# power_sply.net
KiCad netlist of a schematic drawn in EAGLE
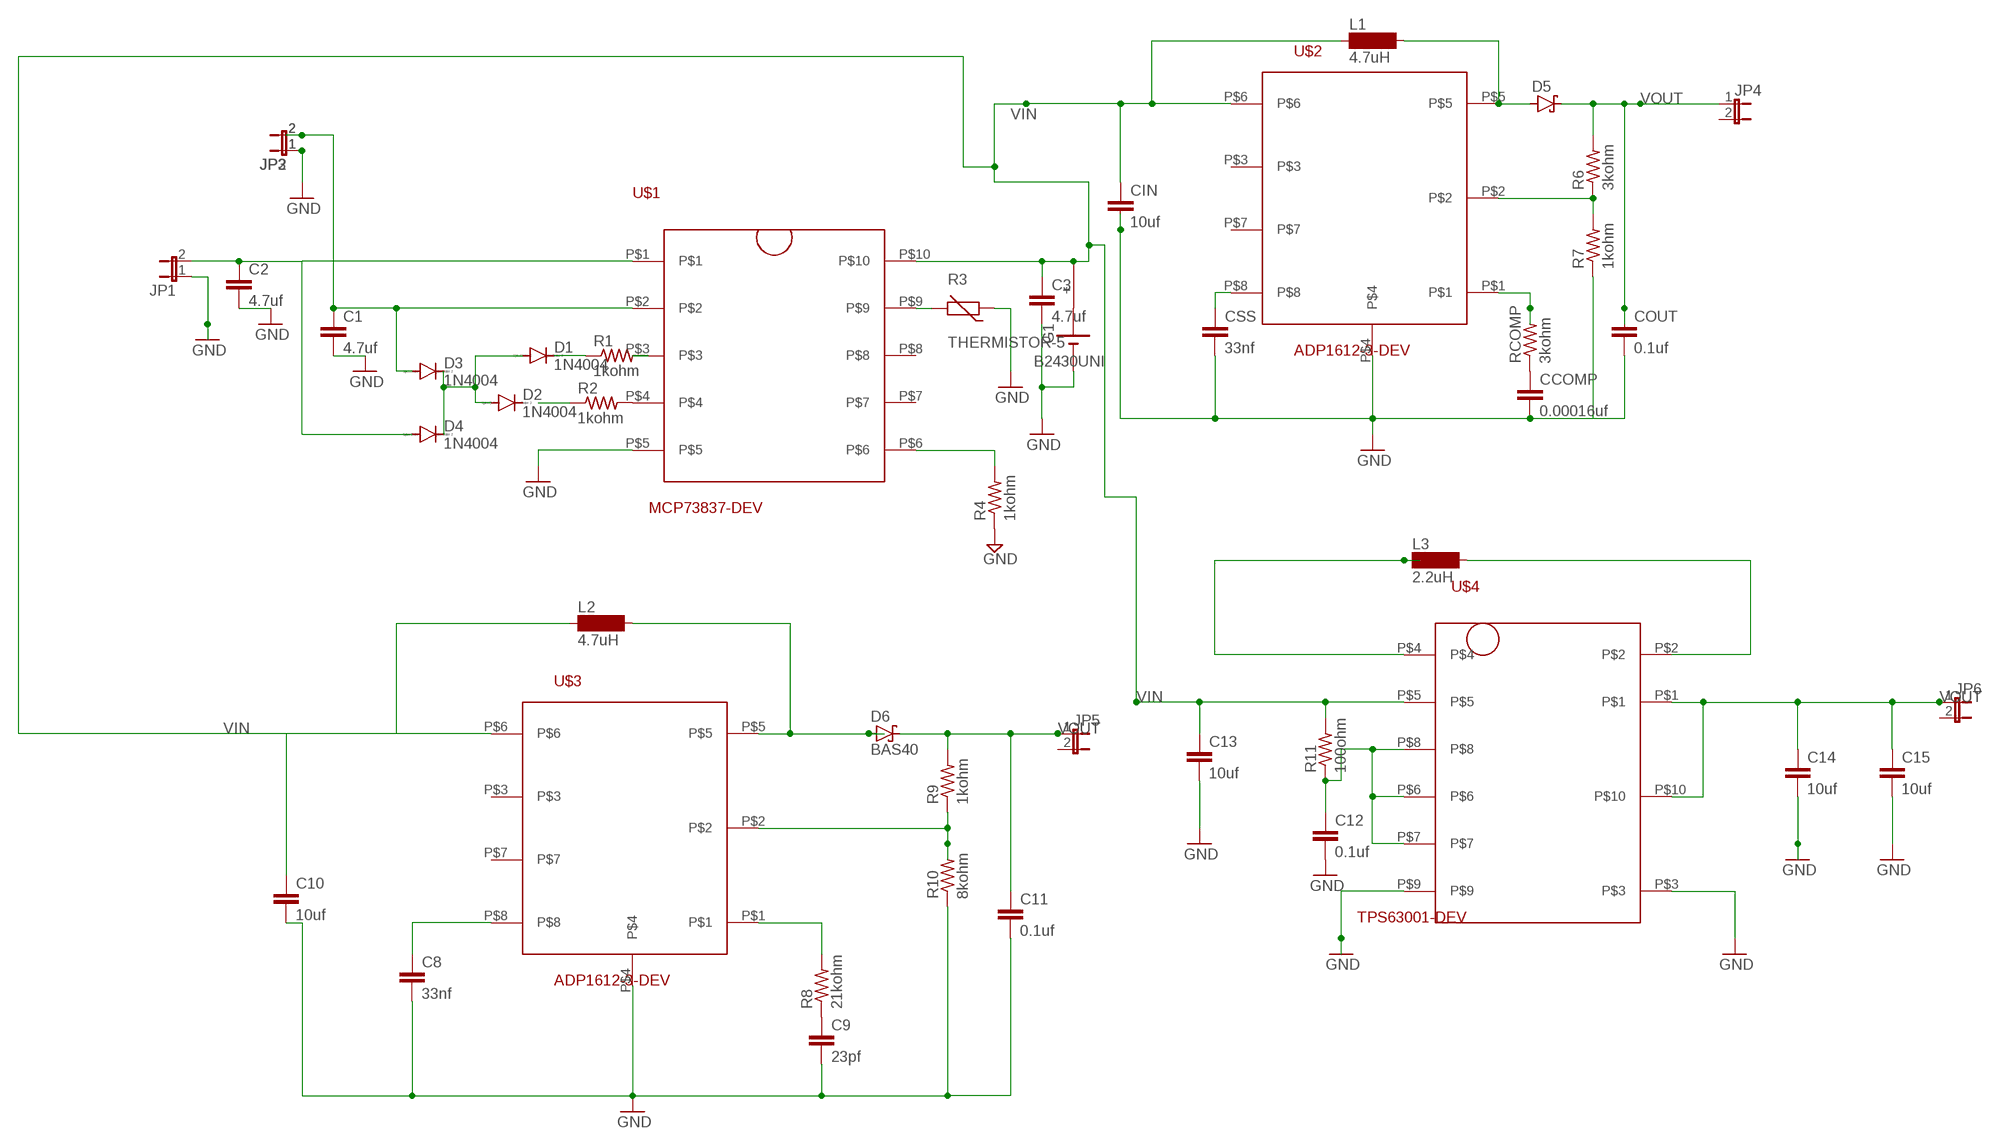
[diagram p0: schematic, sheet 1]

(export (version "E")
  (design (tool "Eeschema 10.0.6"))
  (components
    (comp (ref "C1")
      (value "4.7uf")
      (footprint "eagle-import:C2.5-3")
      (libsource (lib "eagle-import") (part "C2,5-3"))
    )
    (comp (ref "C2")
      (value "4.7uf")
      (footprint "eagle-import:C2.5-3")
      (libsource (lib "eagle-import") (part "C2,5-3"))
    )
    (comp (ref "C3")
      (value "4.7uf")
      (footprint "eagle-import:C2.5-3")
      (libsource (lib "eagle-import") (part "C2,5-3"))
    )
    (comp (ref "C8")
      (value "33nf")
      (footprint "eagle-import:C2.5-3")
      (libsource (lib "eagle-import") (part "C2,5-3"))
    )
    (comp (ref "C9")
      (value "23pf")
      (footprint "eagle-import:C2.5-3")
      (libsource (lib "eagle-import") (part "C2,5-3"))
    )
    (comp (ref "C10")
      (value "10uf")
      (footprint "eagle-import:C2.5-3")
      (libsource (lib "eagle-import") (part "C2,5-3"))
    )
    (comp (ref "C11")
      (value "0.1uf")
      (footprint "eagle-import:C2.5-3")
      (libsource (lib "eagle-import") (part "C2,5-3"))
    )
    (comp (ref "C12")
      (value "0.1uf")
      (footprint "eagle-import:C2.5-3")
      (libsource (lib "eagle-import") (part "C2,5-3"))
    )
    (comp (ref "C13")
      (value "10uf")
      (footprint "eagle-import:C2.5-3")
      (libsource (lib "eagle-import") (part "C2,5-3"))
    )
    (comp (ref "C14")
      (value "10uf")
      (footprint "eagle-import:C2.5-3")
      (libsource (lib "eagle-import") (part "C2,5-3"))
    )
    (comp (ref "C15")
      (value "10uf")
      (footprint "eagle-import:C2.5-3")
      (libsource (lib "eagle-import") (part "C2,5-3"))
    )
    (comp (ref "CCOMP")
      (value "0.00016uf")
      (footprint "eagle-import:C2.5-3")
      (libsource (lib "eagle-import") (part "C2,5-3"))
    )
    (comp (ref "CIN")
      (value "10uf")
      (footprint "eagle-import:C2.5-3")
      (libsource (lib "eagle-import") (part "C2,5-3"))
    )
    (comp (ref "COUT")
      (value "0.1uf")
      (footprint "eagle-import:C2.5-3")
      (libsource (lib "eagle-import") (part "C2,5-3"))
    )
    (comp (ref "CSS")
      (value "33nf")
      (footprint "eagle-import:C2.5-3")
      (libsource (lib "eagle-import") (part "C2,5-3"))
    )
    (comp (ref "D1")
      (value "1N4004")
      (footprint "eagle-import:DO41-10")
      (libsource (lib "eagle-import") (part "1N4004"))
    )
    (comp (ref "D2")
      (value "1N4004")
      (footprint "eagle-import:DO41-10")
      (libsource (lib "eagle-import") (part "1N4004"))
    )
    (comp (ref "D3")
      (value "1N4004")
      (footprint "eagle-import:DO41-10")
      (libsource (lib "eagle-import") (part "1N4004"))
    )
    (comp (ref "D4")
      (value "1N4004")
      (footprint "eagle-import:DO41-10")
      (libsource (lib "eagle-import") (part "1N4004"))
    )
    (comp (ref "D5")
      (value "BAS40")
      (footprint "eagle-import:SOT23")
      (libsource (lib "eagle-import") (part "BAS40"))
    )
    (comp (ref "D6")
      (value "BAS40")
      (footprint "eagle-import:SOT23")
      (libsource (lib "eagle-import") (part "BAS40"))
    )
    (comp (ref "G1")
      (value "B2430UNI")
      (footprint "eagle-import:B2430UNI")
      (libsource (lib "eagle-import") (part "B2430UNI"))
    )
    (comp (ref "JP1")
      (value "JP1E")
      (footprint "eagle-import:JP1")
      (libsource (lib "eagle-import") (part "JP1E"))
    )
    (comp (ref "JP2")
      (value "JP1E")
      (footprint "eagle-import:JP1")
      (libsource (lib "eagle-import") (part "JP1E"))
    )
    (comp (ref "JP3")
      (value "JP1E")
      (footprint "eagle-import:JP1")
      (libsource (lib "eagle-import") (part "JP1E"))
    )
    (comp (ref "JP4")
      (value "JP1E")
      (footprint "eagle-import:JP1")
      (libsource (lib "eagle-import") (part "JP1E"))
    )
    (comp (ref "JP5")
      (value "JP1E")
      (footprint "eagle-import:JP1")
      (libsource (lib "eagle-import") (part "JP1E"))
    )
    (comp (ref "JP6")
      (value "JP1E")
      (footprint "eagle-import:JP1")
      (libsource (lib "eagle-import") (part "JP1E"))
    )
    (comp (ref "L1")
      (value "4.7uH")
      (footprint "eagle-import:MS42")
      (libsource (lib "eagle-import") (part "MS42"))
    )
    (comp (ref "L2")
      (value "4.7uH")
      (footprint "eagle-import:MS42")
      (libsource (lib "eagle-import") (part "MS42"))
    )
    (comp (ref "L3")
      (value "2.2uH")
      (footprint "eagle-import:BS11")
      (libsource (lib "eagle-import") (part "BS11"))
    )
    (comp (ref "R1")
      (value "1kohm")
      (footprint "eagle-import:0204V")
      (libsource (lib "eagle-import") (part "R-US_0204/2V"))
    )
    (comp (ref "R2")
      (value "1kohm")
      (footprint "eagle-import:0204V")
      (libsource (lib "eagle-import") (part "R-US_0204/2V"))
    )
    (comp (ref "R3")
      (value "THERMISTOR-5")
      (footprint "eagle-import:R-5")
      (libsource (lib "eagle-import") (part "THERMISTOR-5"))
    )
    (comp (ref "R4")
      (value "1kohm")
      (footprint "eagle-import:0204V")
      (libsource (lib "eagle-import") (part "R-US_0204/2V"))
    )
    (comp (ref "R6")
      (value "3kohm")
      (footprint "eagle-import:0204V")
      (libsource (lib "eagle-import") (part "R-US_0204/2V"))
    )
    (comp (ref "R7")
      (value "1kohm")
      (footprint "eagle-import:0204V")
      (libsource (lib "eagle-import") (part "R-US_0204/2V"))
    )
    (comp (ref "R8")
      (value "21kohm")
      (footprint "eagle-import:0204V")
      (libsource (lib "eagle-import") (part "R-US_0204/2V"))
    )
    (comp (ref "R9")
      (value "1kohm")
      (footprint "eagle-import:0204V")
      (libsource (lib "eagle-import") (part "R-US_0204/2V"))
    )
    (comp (ref "R10")
      (value "8kohm")
      (footprint "eagle-import:0204V")
      (libsource (lib "eagle-import") (part "R-US_0204/2V"))
    )
    (comp (ref "R11")
      (value "100ohm")
      (footprint "eagle-import:0204V")
      (libsource (lib "eagle-import") (part "R-US_0204/2V"))
    )
    (comp (ref "RCOMP")
      (value "3kohm")
      (footprint "eagle-import:0204V")
      (libsource (lib "eagle-import") (part "R-US_0204/2V"))
    )
    (comp (ref "U$1")
      (value "MCP73837-DEV")
      (footprint "eagle-import:MCP73837-FOOT")
      (libsource (lib "eagle-import") (part "MCP73837-DEV"))
    )
    (comp (ref "U$2")
      (value "ADP1612-3-DEV")
      (footprint "eagle-import:ADP1612-3-FOOT")
      (libsource (lib "eagle-import") (part "ADP1612-3-DEV"))
    )
    (comp (ref "U$3")
      (value "ADP1612-3-DEV")
      (footprint "eagle-import:ADP1612-3-FOOT")
      (libsource (lib "eagle-import") (part "ADP1612-3-DEV"))
    )
    (comp (ref "U$4")
      (value "TPS63001-DEV")
      (footprint "eagle-import:TPS63001-FOOT")
      (libsource (lib "eagle-import") (part "TPS63001-DEV"))
    )
  )
  (nets
    (net (code "1") (name "/VIN") (class "Default")
      (node (ref "C10") (pin "1") (pinfunction "1_1") (pintype "passive"))
      (node (ref "C13") (pin "1") (pinfunction "1_1") (pintype "passive"))
      (node (ref "C3") (pin "1") (pinfunction "1_1") (pintype "passive"))
      (node (ref "CIN") (pin "1") (pinfunction "1_1") (pintype "passive"))
      (node (ref "G1") (pin "+") (pinfunction "+_+") (pintype "passive"))
      (node (ref "L1") (pin "1") (pinfunction "1_1") (pintype "passive"))
      (node (ref "L2") (pin "1") (pinfunction "1_1") (pintype "passive"))
      (node (ref "R11") (pin "2") (pinfunction "2_2") (pintype "passive"))
      (node (ref "U$1") (pin "P$10") (pinfunction "P$10_P$10") (pintype "bidirectional"))
      (node (ref "U$2") (pin "P$6") (pinfunction "P$6_P$6") (pintype "bidirectional"))
      (node (ref "U$3") (pin "P$6") (pinfunction "P$6_P$6") (pintype "bidirectional"))
      (node (ref "U$4") (pin "P$5") (pinfunction "P$5_P$5") (pintype "bidirectional"))
    )
    (net (code "2") (name "/VOUT") (class "Default")
      (node (ref "C11") (pin "1") (pinfunction "1_1") (pintype "passive"))
      (node (ref "C14") (pin "1") (pinfunction "1_1") (pintype "passive"))
      (node (ref "C15") (pin "1") (pinfunction "1_1") (pintype "passive"))
      (node (ref "COUT") (pin "1") (pinfunction "1_1") (pintype "passive"))
      (node (ref "D5") (pin "3") (pinfunction "C_3") (pintype "passive"))
      (node (ref "D6") (pin "3") (pinfunction "C_3") (pintype "passive"))
      (node (ref "JP4") (pin "1") (pinfunction "1_1") (pintype "passive"))
      (node (ref "JP5") (pin "1") (pinfunction "1_1") (pintype "passive"))
      (node (ref "JP6") (pin "1") (pinfunction "1_1") (pintype "passive"))
      (node (ref "R6") (pin "2") (pinfunction "2_2") (pintype "passive"))
      (node (ref "R9") (pin "2") (pinfunction "2_2") (pintype "passive"))
      (node (ref "U$4") (pin "P$1") (pinfunction "P$1_P$1") (pintype "bidirectional"))
      (node (ref "U$4") (pin "P$10") (pinfunction "P$10_P$10") (pintype "bidirectional"))
    )
    (net (code "3") (name "GND") (class "Default")
      (node (ref "C1") (pin "2") (pinfunction "2_2") (pintype "passive"))
      (node (ref "C10") (pin "2") (pinfunction "2_2") (pintype "passive"))
      (node (ref "C11") (pin "2") (pinfunction "2_2") (pintype "passive"))
      (node (ref "C12") (pin "2") (pinfunction "2_2") (pintype "passive"))
      (node (ref "C13") (pin "2") (pinfunction "2_2") (pintype "passive"))
      (node (ref "C14") (pin "2") (pinfunction "2_2") (pintype "passive"))
      (node (ref "C15") (pin "2") (pinfunction "2_2") (pintype "passive"))
      (node (ref "C2") (pin "2") (pinfunction "2_2") (pintype "passive"))
      (node (ref "C3") (pin "2") (pinfunction "2_2") (pintype "passive"))
      (node (ref "C8") (pin "2") (pinfunction "2_2") (pintype "passive"))
      (node (ref "C9") (pin "2") (pinfunction "2_2") (pintype "passive"))
      (node (ref "CCOMP") (pin "2") (pinfunction "2_2") (pintype "passive"))
      (node (ref "CIN") (pin "2") (pinfunction "2_2") (pintype "passive"))
      (node (ref "COUT") (pin "2") (pinfunction "2_2") (pintype "passive"))
      (node (ref "CSS") (pin "2") (pinfunction "2_2") (pintype "passive"))
      (node (ref "G1") (pin "-") (pinfunction "-_-") (pintype "passive"))
      (node (ref "JP1") (pin "1") (pinfunction "1_1") (pintype "passive"))
      (node (ref "JP2") (pin "1") (pinfunction "1_1") (pintype "passive"))
      (node (ref "JP3") (pin "1") (pinfunction "1_1") (pintype "passive"))
      (node (ref "R10") (pin "1") (pinfunction "1_1") (pintype "passive"))
      (node (ref "R3") (pin "1") (pinfunction "1_1") (pintype "passive"))
      (node (ref "R4") (pin "1") (pinfunction "1_1") (pintype "passive"))
      (node (ref "U$1") (pin "P$5") (pinfunction "P$5_P$5") (pintype "bidirectional"))
      (node (ref "U$2") (pin "P$4") (pinfunction "P$4_P$4") (pintype "bidirectional"))
      (node (ref "U$3") (pin "P$4") (pinfunction "P$4_P$4") (pintype "bidirectional"))
      (node (ref "U$4") (pin "P$3") (pinfunction "P$3_P$3") (pintype "bidirectional"))
      (node (ref "U$4") (pin "P$9") (pinfunction "P$9_P$9") (pintype "bidirectional"))
    )
    (net (code "4") (name "Net-(C1-Pad1)") (class "Default")
      (node (ref "C1") (pin "1") (pinfunction "1_1") (pintype "passive"))
      (node (ref "D3") (pin "A") (pinfunction "A_A") (pintype "passive"))
      (node (ref "JP2") (pin "2") (pinfunction "2_2") (pintype "passive"))
      (node (ref "JP3") (pin "2") (pinfunction "2_2") (pintype "passive"))
      (node (ref "U$1") (pin "P$2") (pinfunction "P$2_P$2") (pintype "bidirectional"))
    )
    (net (code "5") (name "Net-(C2-Pad1)") (class "Default")
      (node (ref "C2") (pin "1") (pinfunction "1_1") (pintype "passive"))
      (node (ref "D4") (pin "A") (pinfunction "A_A") (pintype "passive"))
      (node (ref "JP1") (pin "2") (pinfunction "2_2") (pintype "passive"))
      (node (ref "U$1") (pin "P$1") (pinfunction "P$1_P$1") (pintype "bidirectional"))
    )
    (net (code "6") (name "Net-(C8-Pad1)") (class "Default")
      (node (ref "C8") (pin "1") (pinfunction "1_1") (pintype "passive"))
      (node (ref "U$3") (pin "P$8") (pinfunction "P$8_P$8") (pintype "bidirectional"))
    )
    (net (code "7") (name "Net-(C9-Pad1)") (class "Default")
      (node (ref "C9") (pin "1") (pinfunction "1_1") (pintype "passive"))
      (node (ref "R8") (pin "1") (pinfunction "1_1") (pintype "passive"))
    )
    (net (code "8") (name "Net-(C12-Pad1)") (class "Default")
      (node (ref "C12") (pin "1") (pinfunction "1_1") (pintype "passive"))
      (node (ref "R11") (pin "1") (pinfunction "1_1") (pintype "passive"))
      (node (ref "U$4") (pin "P$6") (pinfunction "P$6_P$6") (pintype "bidirectional"))
      (node (ref "U$4") (pin "P$7") (pinfunction "P$7_P$7") (pintype "bidirectional"))
      (node (ref "U$4") (pin "P$8") (pinfunction "P$8_P$8") (pintype "bidirectional"))
    )
    (net (code "9") (name "Net-(CCOMP-Pad1)") (class "Default")
      (node (ref "CCOMP") (pin "1") (pinfunction "1_1") (pintype "passive"))
      (node (ref "RCOMP") (pin "1") (pinfunction "1_1") (pintype "passive"))
    )
    (net (code "10") (name "Net-(CSS-Pad1)") (class "Default")
      (node (ref "CSS") (pin "1") (pinfunction "1_1") (pintype "passive"))
      (node (ref "U$2") (pin "P$8") (pinfunction "P$8_P$8") (pintype "bidirectional"))
    )
    (net (code "11") (name "Net-(D1-PadA)") (class "Default")
      (node (ref "D1") (pin "A") (pinfunction "A_A") (pintype "passive"))
      (node (ref "D2") (pin "A") (pinfunction "A_A") (pintype "passive"))
      (node (ref "D3") (pin "C") (pinfunction "C_C") (pintype "passive"))
      (node (ref "D4") (pin "C") (pinfunction "C_C") (pintype "passive"))
    )
    (net (code "12") (name "Net-(D1-PadC)") (class "Default")
      (node (ref "D1") (pin "C") (pinfunction "C_C") (pintype "passive"))
      (node (ref "R1") (pin "1") (pinfunction "1_1") (pintype "passive"))
    )
    (net (code "13") (name "Net-(D5-A)") (class "Default")
      (node (ref "D5") (pin "1") (pinfunction "A_1") (pintype "passive"))
      (node (ref "L1") (pin "2") (pinfunction "2_2") (pintype "passive"))
      (node (ref "U$2") (pin "P$5") (pinfunction "P$5_P$5") (pintype "bidirectional"))
    )
    (net (code "14") (name "Net-(D6-A)") (class "Default")
      (node (ref "D6") (pin "1") (pinfunction "A_1") (pintype "passive"))
      (node (ref "L2") (pin "2") (pinfunction "2_2") (pintype "passive"))
      (node (ref "U$3") (pin "P$5") (pinfunction "P$5_P$5") (pintype "bidirectional"))
    )
    (net (code "15") (name "Net-(L3-Pad1)") (class "Default")
      (node (ref "L3") (pin "1") (pinfunction "1_1") (pintype "passive"))
      (node (ref "U$4") (pin "P$4") (pinfunction "P$4_P$4") (pintype "bidirectional"))
    )
    (net (code "16") (name "Net-(L3-Pad2)") (class "Default")
      (node (ref "L3") (pin "2") (pinfunction "2_2") (pintype "passive"))
      (node (ref "U$4") (pin "P$2") (pinfunction "P$2_P$2") (pintype "bidirectional"))
    )
    (net (code "17") (name "Net-(R1-Pad2)") (class "Default")
      (node (ref "R1") (pin "2") (pinfunction "2_2") (pintype "passive"))
      (node (ref "U$1") (pin "P$3") (pinfunction "P$3_P$3") (pintype "bidirectional"))
    )
    (net (code "18") (name "Net-(R2-Pad2)") (class "Default")
      (node (ref "R2") (pin "2") (pinfunction "2_2") (pintype "passive"))
      (node (ref "U$1") (pin "P$4") (pinfunction "P$4_P$4") (pintype "bidirectional"))
    )
    (net (code "19") (name "Net-(R3-Pad2)") (class "Default")
      (node (ref "R3") (pin "2") (pinfunction "2_2") (pintype "passive"))
      (node (ref "U$1") (pin "P$9") (pinfunction "P$9_P$9") (pintype "bidirectional"))
    )
    (net (code "20") (name "Net-(R4-Pad2)") (class "Default")
      (node (ref "R4") (pin "2") (pinfunction "2_2") (pintype "passive"))
      (node (ref "U$1") (pin "P$6") (pinfunction "P$6_P$6") (pintype "bidirectional"))
    )
    (net (code "21") (name "Net-(R6-Pad1)") (class "Default")
      (node (ref "R6") (pin "1") (pinfunction "1_1") (pintype "passive"))
      (node (ref "R7") (pin "2") (pinfunction "2_2") (pintype "passive"))
      (node (ref "U$2") (pin "P$2") (pinfunction "P$2_P$2") (pintype "bidirectional"))
    )
    (net (code "22") (name "Net-(R8-Pad2)") (class "Default")
      (node (ref "R8") (pin "2") (pinfunction "2_2") (pintype "passive"))
      (node (ref "U$3") (pin "P$1") (pinfunction "P$1_P$1") (pintype "bidirectional"))
    )
    (net (code "23") (name "Net-(R10-Pad2)") (class "Default")
      (node (ref "R10") (pin "2") (pinfunction "2_2") (pintype "passive"))
      (node (ref "R9") (pin "1") (pinfunction "1_1") (pintype "passive"))
      (node (ref "U$3") (pin "P$2") (pinfunction "P$2_P$2") (pintype "bidirectional"))
    )
    (net (code "24") (name "Net-(RCOMP-Pad2)") (class "Default")
      (node (ref "RCOMP") (pin "2") (pinfunction "2_2") (pintype "passive"))
      (node (ref "U$2") (pin "P$1") (pinfunction "P$1_P$1") (pintype "bidirectional"))
    )
    (net (code "25") (name "unconnected-(D2-PadC)") (class "Default")
      (node (ref "D2") (pin "C") (pinfunction "C_C") (pintype "passive"))
    )
    (net (code "26") (name "unconnected-(G1-+-Pad+@1)") (class "Default")
      (node (ref "G1") (pin "+@1") (pinfunction "+_+@1") (pintype "passive"))
    )
    (net (code "27") (name "unconnected-(G1-+-Pad+@2)") (class "Default")
      (node (ref "G1") (pin "+@2") (pinfunction "+_+@2") (pintype "passive"))
    )
    (net (code "28") (name "unconnected-(G1-+-Pad+@3)") (class "Default")
      (node (ref "G1") (pin "+@3") (pinfunction "+_+@3") (pintype "passive"))
    )
    (net (code "29") (name "unconnected-(G1-+-Pad+@4)") (class "Default")
      (node (ref "G1") (pin "+@4") (pinfunction "+_+@4") (pintype "passive"))
    )
    (net (code "30") (name "unconnected-(G1---Pad-@1)") (class "Default")
      (node (ref "G1") (pin "-@1") (pinfunction "-_-@1") (pintype "passive"))
    )
    (net (code "31") (name "unconnected-(JP4-Pad2)") (class "Default")
      (node (ref "JP4") (pin "2") (pinfunction "2_2") (pintype "passive"))
    )
    (net (code "32") (name "unconnected-(JP5-Pad2)") (class "Default")
      (node (ref "JP5") (pin "2") (pinfunction "2_2") (pintype "passive"))
    )
    (net (code "33") (name "unconnected-(JP6-Pad2)") (class "Default")
      (node (ref "JP6") (pin "2") (pinfunction "2_2") (pintype "passive"))
    )
    (net (code "34") (name "unconnected-(R2-Pad1)") (class "Default")
      (node (ref "R2") (pin "1") (pinfunction "1_1") (pintype "passive"))
    )
    (net (code "35") (name "unconnected-(R7-Pad1)") (class "Default")
      (node (ref "R7") (pin "1") (pinfunction "1_1") (pintype "passive"))
    )
    (net (code "36") (name "unconnected-(U$1-PadP$7)") (class "Default")
      (node (ref "U$1") (pin "P$7") (pinfunction "P$7_P$7") (pintype "bidirectional"))
    )
    (net (code "37") (name "unconnected-(U$1-PadP$8)") (class "Default")
      (node (ref "U$1") (pin "P$8") (pinfunction "P$8_P$8") (pintype "bidirectional"))
    )
    (net (code "38") (name "unconnected-(U$2-PadP$3)") (class "Default")
      (node (ref "U$2") (pin "P$3") (pinfunction "P$3_P$3") (pintype "bidirectional"))
    )
    (net (code "39") (name "unconnected-(U$2-PadP$7)") (class "Default")
      (node (ref "U$2") (pin "P$7") (pinfunction "P$7_P$7") (pintype "bidirectional"))
    )
    (net (code "40") (name "unconnected-(U$3-PadP$3)") (class "Default")
      (node (ref "U$3") (pin "P$3") (pinfunction "P$3_P$3") (pintype "bidirectional"))
    )
    (net (code "41") (name "unconnected-(U$3-PadP$7)") (class "Default")
      (node (ref "U$3") (pin "P$7") (pinfunction "P$7_P$7") (pintype "bidirectional"))
    )
  )
)
